# boosst_revB.net
KiCad netlist of a schematic drawn in EAGLE
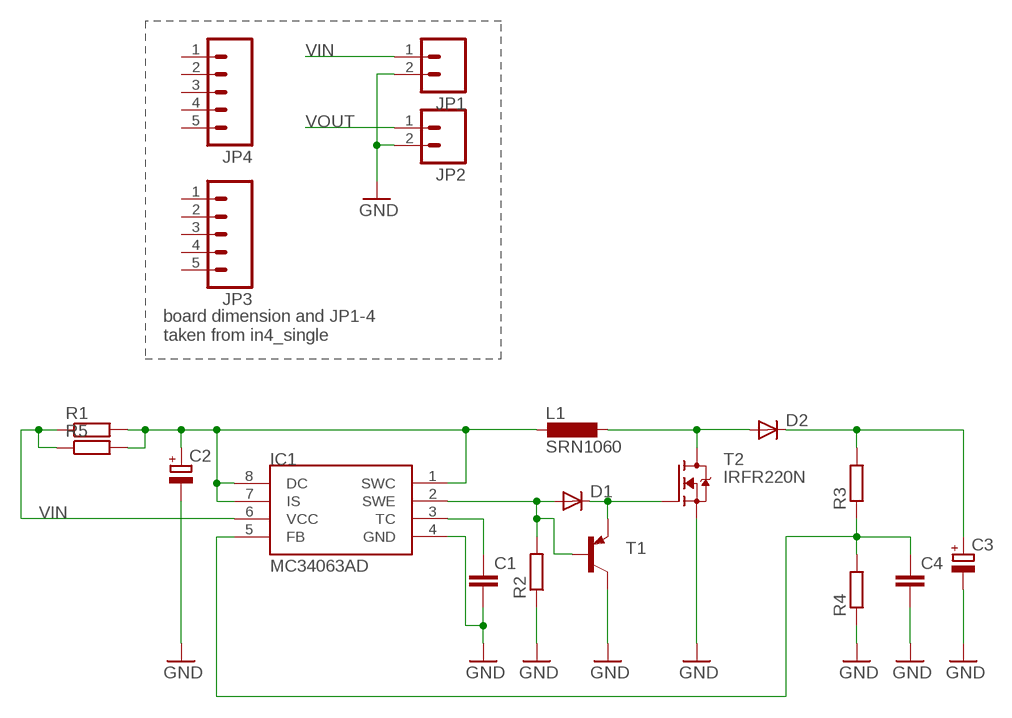
[diagram p0: schematic, sheet 1]

(export (version "E")
  (design (tool "Eeschema 10.0.6"))
  (components
    (comp (ref "C1")
      (value "C-EUC1206")
      (footprint "eagle-import:C1206")
      (libsource (lib "eagle-import") (part "C-EUC1206"))
    )
    (comp (ref "C2")
      (value "CPOL-EUE2.5-6")
      (footprint "eagle-import:E2,5-6")
      (libsource (lib "eagle-import") (part "CPOL-EUE2.5-6"))
    )
    (comp (ref "C3")
      (value "CPOL-EUE2,5-6E")
      (footprint "eagle-import:E2,5-6E")
      (libsource (lib "eagle-import") (part "CPOL-EUE2,5-6E"))
    )
    (comp (ref "C4")
      (value "C-EUC1206")
      (footprint "eagle-import:C1206")
      (libsource (lib "eagle-import") (part "C-EUC1206"))
    )
    (comp (ref "D1")
      (value "DIODE-SOD123")
      (footprint "eagle-import:SOD123")
      (libsource (lib "eagle-import") (part "DIODE-SOD123"))
    )
    (comp (ref "D2")
      (value "DIODE-SMB")
      (footprint "eagle-import:SMB")
      (libsource (lib "eagle-import") (part "DIODE-SMB"))
    )
    (comp (ref "IC1")
      (value "MC34063AD")
      (footprint "eagle-import:SOIC8")
      (libsource (lib "eagle-import") (part "MC34063AD"))
    )
    (comp (ref "JP1")
      (value "M02PTH")
      (footprint "eagle-import:1X02")
      (libsource (lib "eagle-import") (part "M02PTH"))
    )
    (comp (ref "JP2")
      (value "M02PTH")
      (footprint "eagle-import:1X02")
      (libsource (lib "eagle-import") (part "M02PTH"))
    )
    (comp (ref "JP3")
      (value "M05PTH")
      (footprint "eagle-import:1X05")
      (libsource (lib "eagle-import") (part "M05PTH"))
    )
    (comp (ref "JP4")
      (value "M05PTH")
      (footprint "eagle-import:1X05")
      (libsource (lib "eagle-import") (part "M05PTH"))
    )
    (comp (ref "L1")
      (value "SRN1060")
      (footprint "eagle-import:SRN1060")
      (libsource (lib "eagle-import") (part "SRN1060"))
    )
    (comp (ref "R1")
      (value "R-EU_M1206")
      (footprint "eagle-import:M1206")
      (libsource (lib "eagle-import") (part "R-EU_M1206"))
    )
    (comp (ref "R2")
      (value "R-EU_R1206")
      (footprint "eagle-import:R1206")
      (libsource (lib "eagle-import") (part "R-EU_R1206"))
    )
    (comp (ref "R3")
      (value "R-EU_R1206")
      (footprint "eagle-import:R1206")
      (libsource (lib "eagle-import") (part "R-EU_R1206"))
    )
    (comp (ref "R4")
      (value "R-EU_R1206")
      (footprint "eagle-import:R1206")
      (libsource (lib "eagle-import") (part "R-EU_R1206"))
    )
    (comp (ref "R5")
      (value "R-EU_M1206")
      (footprint "eagle-import:M1206")
      (libsource (lib "eagle-import") (part "R-EU_M1206"))
    )
    (comp (ref "T1")
      (value "MMBT3906LT1-PNP-SOT23-BEC")
      (footprint "eagle-import:SOT23-BEC")
      (libsource (lib "eagle-import") (part "-PNP-SOT23-BECMMBT3906LT1"))
    )
    (comp (ref "T2")
      (value "IRFR220N")
      (footprint "eagle-import:DPACK")
      (libsource (lib "eagle-import") (part "IRFR220N"))
    )
  )
  (nets
    (net (code "1") (name "/VIN") (class "Default")
      (node (ref "IC1") (pin "6") (pinfunction "VCC_6") (pintype "passive"))
      (node (ref "JP1") (pin "1") (pinfunction "1_1") (pintype "passive"))
      (node (ref "R1") (pin "1") (pinfunction "1_1") (pintype "passive"))
      (node (ref "R5") (pin "1") (pinfunction "1_1") (pintype "passive"))
    )
    (net (code "2") (name "/VOUT") (class "Default")
      (node (ref "C3") (pin "+") (pinfunction "+_+") (pintype "passive"))
      (node (ref "D2") (pin "C") (pinfunction "C_C") (pintype "passive"))
      (node (ref "JP2") (pin "1") (pinfunction "1_1") (pintype "passive"))
      (node (ref "R3") (pin "2") (pinfunction "2_2") (pintype "passive"))
    )
    (net (code "3") (name "GND") (class "Default")
      (node (ref "C1") (pin "2") (pinfunction "2_2") (pintype "passive"))
      (node (ref "C2") (pin "-") (pinfunction "-_-") (pintype "passive"))
      (node (ref "C3") (pin "-") (pinfunction "-_-") (pintype "passive"))
      (node (ref "C4") (pin "2") (pinfunction "2_2") (pintype "passive"))
      (node (ref "IC1") (pin "4") (pinfunction "GND_4") (pintype "passive"))
      (node (ref "JP1") (pin "2") (pinfunction "2_2") (pintype "passive"))
      (node (ref "JP2") (pin "2") (pinfunction "2_2") (pintype "passive"))
      (node (ref "R2") (pin "1") (pinfunction "1_1") (pintype "passive"))
      (node (ref "R4") (pin "1") (pinfunction "1_1") (pintype "passive"))
      (node (ref "T1") (pin "C") (pinfunction "C_C") (pintype "passive"))
      (node (ref "T2") (pin "3") (pinfunction "S_3") (pintype "passive"))
    )
    (net (code "4") (name "Net-(IC1-DC)") (class "Default")
      (node (ref "C2") (pin "+") (pinfunction "+_+") (pintype "passive"))
      (node (ref "IC1") (pin "1") (pinfunction "SWC_1") (pintype "passive"))
      (node (ref "IC1") (pin "7") (pinfunction "IS_7") (pintype "passive"))
      (node (ref "IC1") (pin "8") (pinfunction "DC_8") (pintype "passive"))
      (node (ref "L1") (pin "P$2") (pinfunction "2_P$2") (pintype "passive"))
      (node (ref "R1") (pin "2") (pinfunction "2_2") (pintype "passive"))
      (node (ref "R5") (pin "2") (pinfunction "2_2") (pintype "passive"))
    )
    (net (code "5") (name "Net-(IC1-FB)") (class "Default")
      (node (ref "C4") (pin "1") (pinfunction "1_1") (pintype "passive"))
      (node (ref "IC1") (pin "5") (pinfunction "FB_5") (pintype "passive"))
      (node (ref "R3") (pin "1") (pinfunction "1_1") (pintype "passive"))
      (node (ref "R4") (pin "2") (pinfunction "2_2") (pintype "passive"))
    )
    (net (code "6") (name "Net-(IC1-SWE)") (class "Default")
      (node (ref "D1") (pin "A") (pinfunction "A_A") (pintype "passive"))
      (node (ref "IC1") (pin "2") (pinfunction "SWE_2") (pintype "passive"))
      (node (ref "R2") (pin "2") (pinfunction "2_2") (pintype "passive"))
      (node (ref "T1") (pin "B") (pinfunction "B_B") (pintype "passive"))
    )
    (net (code "7") (name "Net-(IC1-TC)") (class "Default")
      (node (ref "C1") (pin "1") (pinfunction "1_1") (pintype "passive"))
      (node (ref "IC1") (pin "3") (pinfunction "TC_3") (pintype "passive"))
    )
    (net (code "8") (name "Net-(L1-1)") (class "Default")
      (node (ref "D2") (pin "A") (pinfunction "A_A") (pintype "passive"))
      (node (ref "L1") (pin "P$1") (pinfunction "1_P$1") (pintype "passive"))
      (node (ref "T2") (pin "4") (pinfunction "D_4") (pintype "passive"))
    )
    (net (code "9") (name "Net-(T2-G)") (class "Default")
      (node (ref "D1") (pin "C") (pinfunction "C_C") (pintype "passive"))
      (node (ref "T1") (pin "E") (pinfunction "E_E") (pintype "passive"))
      (node (ref "T2") (pin "1") (pinfunction "G_1") (pintype "passive"))
    )
    (net (code "10") (name "unconnected-(JP3-Pad1)") (class "Default")
      (node (ref "JP3") (pin "1") (pinfunction "1_1") (pintype "passive"))
    )
    (net (code "11") (name "unconnected-(JP3-Pad2)") (class "Default")
      (node (ref "JP3") (pin "2") (pinfunction "2_2") (pintype "passive"))
    )
    (net (code "12") (name "unconnected-(JP3-Pad3)") (class "Default")
      (node (ref "JP3") (pin "3") (pinfunction "3_3") (pintype "passive"))
    )
    (net (code "13") (name "unconnected-(JP3-Pad4)") (class "Default")
      (node (ref "JP3") (pin "4") (pinfunction "4_4") (pintype "passive"))
    )
    (net (code "14") (name "unconnected-(JP3-Pad5)") (class "Default")
      (node (ref "JP3") (pin "5") (pinfunction "5_5") (pintype "passive"))
    )
    (net (code "15") (name "unconnected-(JP4-Pad1)") (class "Default")
      (node (ref "JP4") (pin "1") (pinfunction "1_1") (pintype "passive"))
    )
    (net (code "16") (name "unconnected-(JP4-Pad2)") (class "Default")
      (node (ref "JP4") (pin "2") (pinfunction "2_2") (pintype "passive"))
    )
    (net (code "17") (name "unconnected-(JP4-Pad3)") (class "Default")
      (node (ref "JP4") (pin "3") (pinfunction "3_3") (pintype "passive"))
    )
    (net (code "18") (name "unconnected-(JP4-Pad4)") (class "Default")
      (node (ref "JP4") (pin "4") (pinfunction "4_4") (pintype "passive"))
    )
    (net (code "19") (name "unconnected-(JP4-Pad5)") (class "Default")
      (node (ref "JP4") (pin "5") (pinfunction "5_5") (pintype "passive"))
    )
  )
)
